# 08_Peripherral.net
KiCad netlist of a schematic drawn in Altium Designer
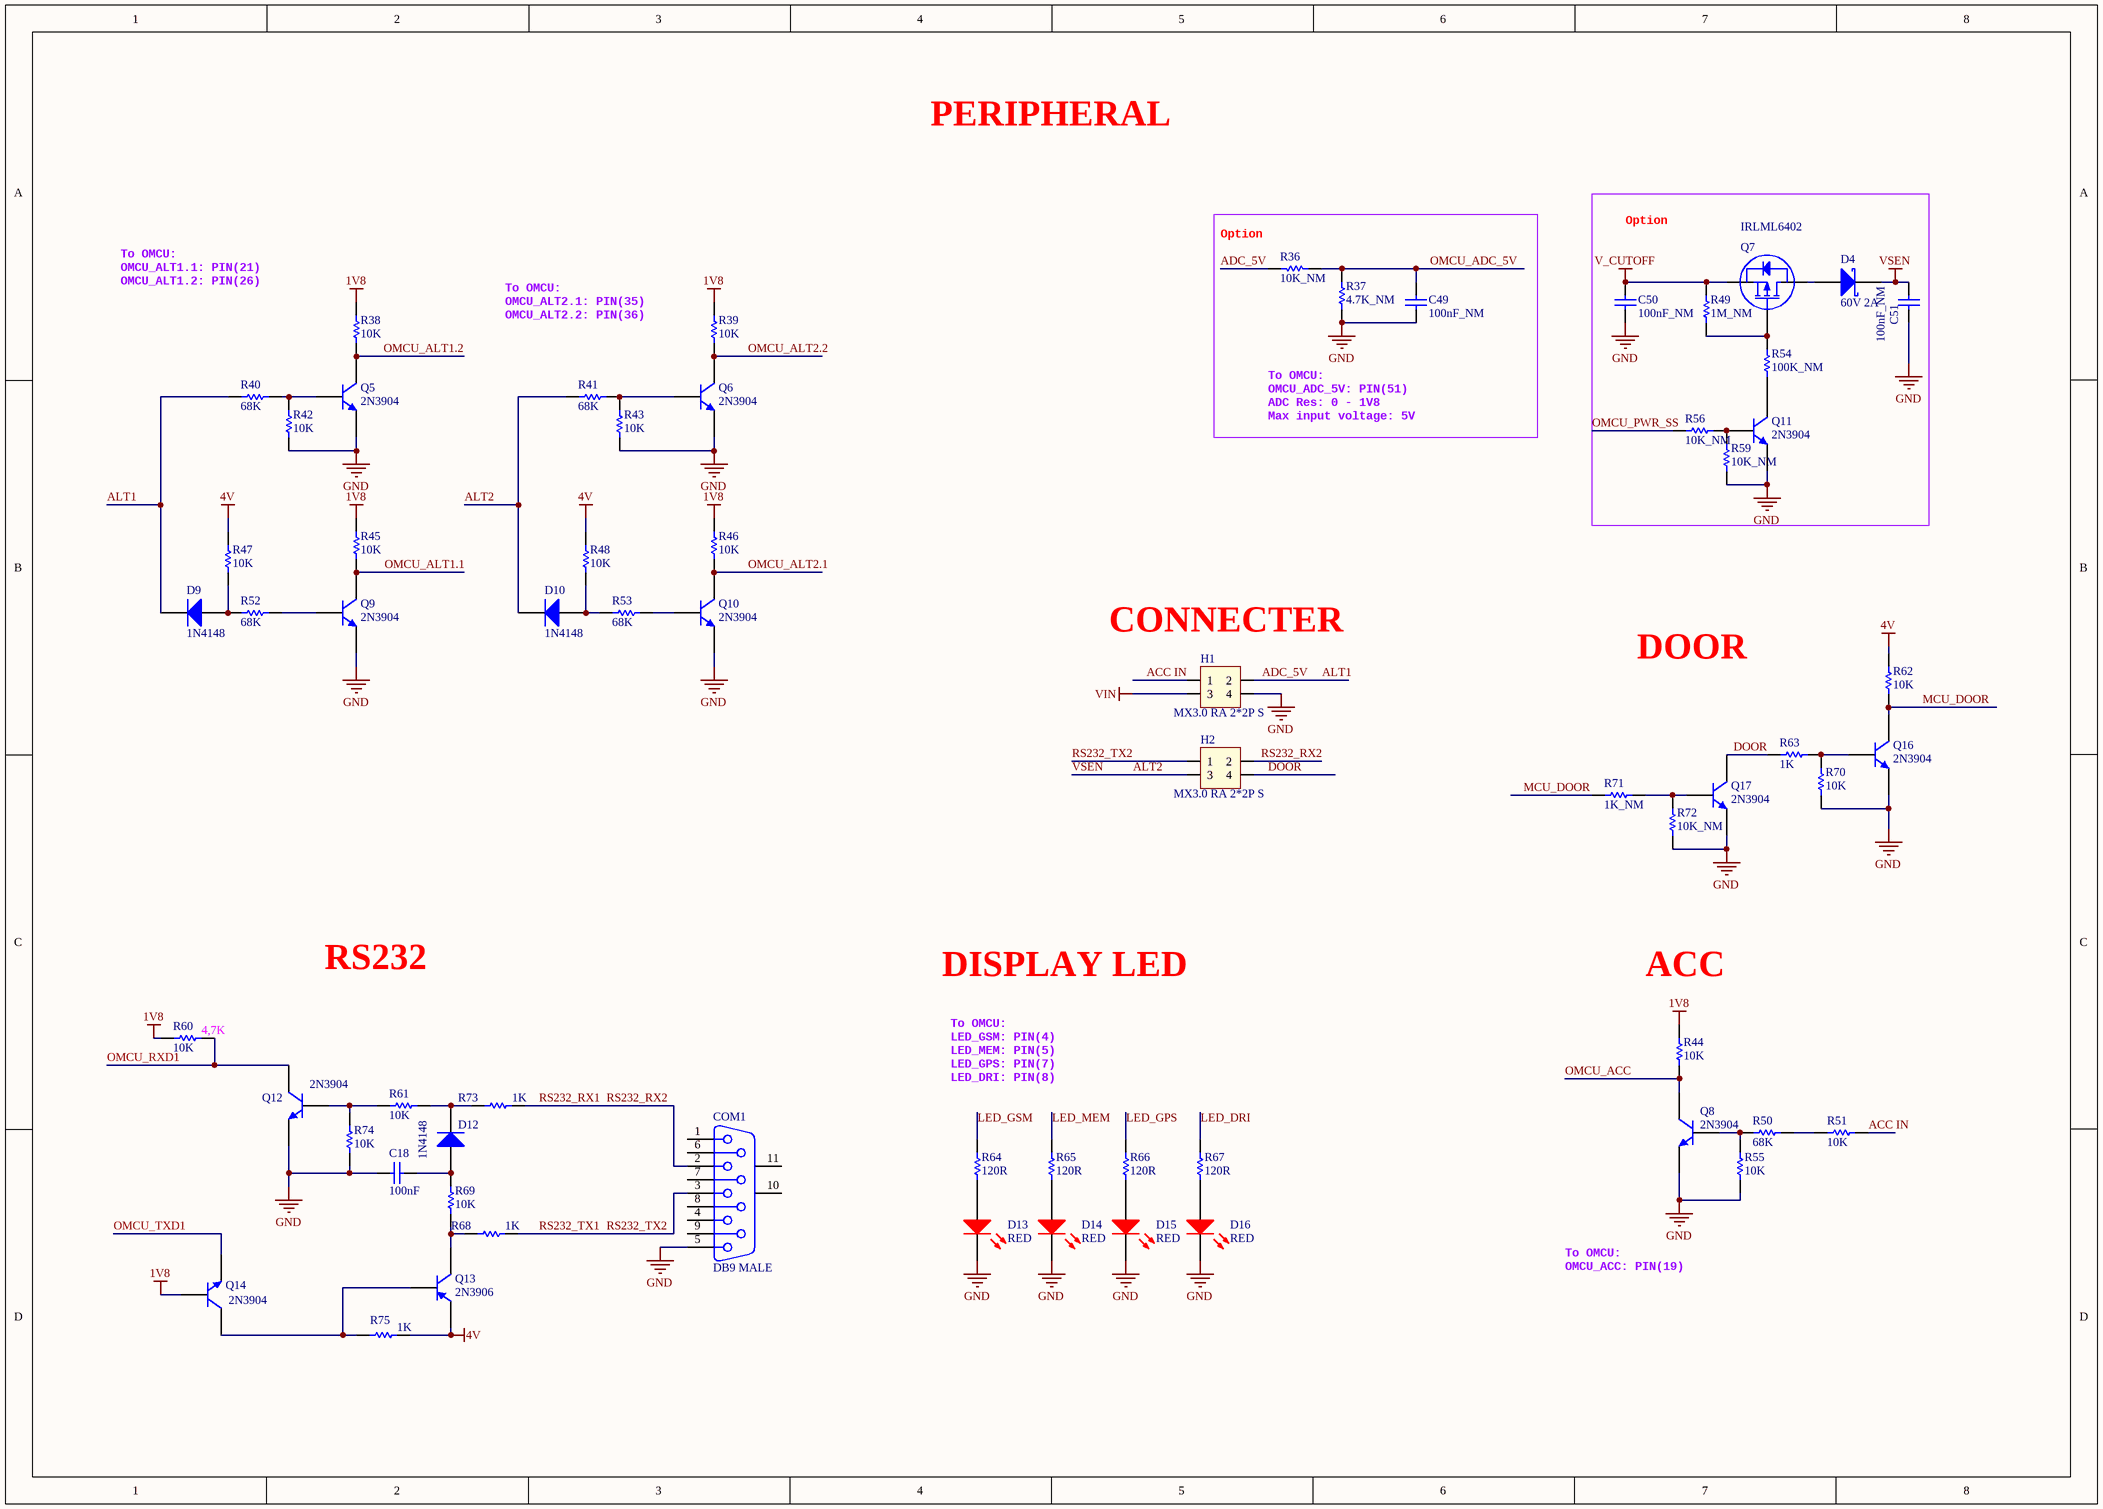
[diagram p0: 08 Peripherral.SchDoc]

(export (version "E")
  (design (tool "Eeschema 10.0.6"))
  (components
    (comp (ref "C18")
      (value "100nF")
      (footprint "0603 - C")
      (description "CAP CER 100nF 50V C0G/NP0 0603")
      (fields (field (name "MPN") "CL10C104JB8NNNC") (field (name "MFR") "SAMSUNG"))
      (libsource (lib "Library_Chip") (part "Cap 0603 100nF"))
    )
    (comp (ref "C49")
      (value "100nF_NM")
      (footprint "0603 - C")
      (description "CAP CER 100nF 50V C0G/NP0 0603")
      (fields (field (name "VOLTAGE") "50V") (field (name "MPN") "CL10C104JB8NNNC"))
      (libsource (lib "Library_Chip") (part "Cap 0603 100nF"))
    )
    (comp (ref "C50")
      (value "100nF_NM")
      (footprint "0603 - C")
      (description "CAP CER 100nF 50V C0G/NP0 0603")
      (fields (field (name "MPN") "CL10C104JB8NNNC") (field (name "MFR") "SAMSUNG"))
      (libsource (lib "Library_Chip") (part "Cap 0603 100nF"))
    )
    (comp (ref "C51")
      (value "100nF_NM")
      (footprint "0603 - C")
      (description "CAP CER 100nF 50V C0G/NP0 0603")
      (fields (field (name "MPN") "CL10C104JB8NNNC") (field (name "MFR") "SAMSUNG"))
      (libsource (lib "Library_Chip") (part "Cap 0603 100nF"))
    )
    (comp (ref "COM1")
      (value "DB9 MALE")
      (footprint "DSB 9M-SM")
      (description "CONN D-SUB PLUG 9POS PNL MNT")
      (fields (field (name "MPN") "772-E09-103R001") (field (name "MFR") "Norcomp Inc."))
      (libsource (lib "Library_ Connector") (part "DB9M S"))
    )
    (comp (ref "D4")
      (value "60V 2A")
      (footprint "SOD-123")
      (description "DIODE SCHOTTKY 60V 2A SOD123W")
      (fields (field (name "MPN") "PMEG6020ER,115") (field (name "MFR") "NXP"))
      (libsource (lib "Library_Chip") (part "Diode PMEG6020ER"))
    )
    (comp (ref "D9")
      (value "1N4148")
      (footprint "SOD-123")
      (description "DIODE GEN PURP 100V 300MA SOD123")
      (fields (field (name "MPN") "1N4148W-7-F") (field (name "MFR") "DIODES"))
      (libsource (lib "Library_Chip") (part "Diode 1N4148"))
    )
    (comp (ref "D10")
      (value "1N4148")
      (footprint "SOD-123")
      (description "DIODE GEN PURP 100V 300MA SOD123")
      (fields (field (name "MPN") "1N4148W-7-F") (field (name "MFR") "DIODES"))
      (libsource (lib "Library_Chip") (part "Diode 1N4148"))
    )
    (comp (ref "D12")
      (value "1N4148")
      (footprint "SOD-123")
      (description "DIODE GEN PURP 100V 300MA SOD123")
      (fields (field (name "MPN") "1N4148W-7-F") (field (name "MFR") "DIODES"))
      (libsource (lib "Library_Chip") (part "Diode 1N4148"))
    )
    (comp (ref "D13")
      (value "RED")
      (footprint "LED - 0603 - R")
      (description "LED RED CLEAR 0603 SMD")
      (fields (field (name "MFR") "Everlight") (field (name "MPN") "QTLP601CRTR"))
      (libsource (lib "Library_Chip") (part "LED 0603 RED"))
    )
    (comp (ref "D14")
      (value "RED")
      (footprint "LED - 0603 - R")
      (description "LED RED CLEAR 0603 SMD")
      (fields (field (name "MFR") "Everlight") (field (name "MPN") "QTLP601CRTR"))
      (libsource (lib "Library_Chip") (part "LED 0603 RED"))
    )
    (comp (ref "D15")
      (value "RED")
      (footprint "LED - 0603 - R")
      (description "LED RED CLEAR 0603 SMD")
      (fields (field (name "MFR") "Everlight") (field (name "MPN") "QTLP601CRTR"))
      (libsource (lib "Library_Chip") (part "LED 0603 RED"))
    )
    (comp (ref "D16")
      (value "RED")
      (footprint "LED - 0603 - R")
      (description "LED RED CLEAR 0603 SMD")
      (fields (field (name "MFR") "Everlight") (field (name "MPN") "QTLP601CRTR"))
      (libsource (lib "Library_Chip") (part "LED 0603 RED"))
    )
    (comp (ref "H1")
      (value "MX3.0 RA 2*2P S")
      (footprint "43045-M3045-2x2-B")
      (description "Micro-Fit 3.0™ Straight Header, 3.00mm Pitch, Dual Row, 4 Circuits")
      (fields (field (name "MPN") "M3045-2x2-B") (field (name "MFR") "China"))
      (libsource (lib "Library_ Connector") (part "HD2x2 S"))
    )
    (comp (ref "H2")
      (value "MX3.0 RA 2*2P S")
      (footprint "43045-M3045-2x2-B")
      (description "Micro-Fit 3.0™ Straight Header, 3.00mm Pitch, Dual Row, 4 Circuits")
      (fields (field (name "MPN") "M3045-2x2-B") (field (name "MFR") "China"))
      (libsource (lib "Library_ Connector") (part "HD2x2 S"))
    )
    (comp (ref "Q5")
      (value "2N3904")
      (footprint "SOT23B")
      (description "TRANS NPN 40V 0.2A SOT-23")
      (fields (field (name "MPN") "MMBT3904") (field (name "MFR") "Fairchild"))
      (libsource (lib "Library_Chip") (part "Transistor 2N3904"))
    )
    (comp (ref "Q6")
      (value "2N3904")
      (footprint "SOT23B")
      (description "TRANS NPN 40V 0.2A SOT-23")
      (fields (field (name "MPN") "MMBT3904") (field (name "MFR") "Fairchild"))
      (libsource (lib "Library_Chip") (part "Transistor 2N3904"))
    )
    (comp (ref "Q7")
      (value "IRLML6402")
      (footprint "SOT23B")
      (description "MOSFET P-CH 30V 3.6A SOT-23-3")
      (fields (field (name "MPN") "IRLML6402TRPBF") (field (name "MFR") "Infineon Technologies"))
      (libsource (lib "Library") (part "IRLML6402TRPBF"))
    )
    (comp (ref "Q8")
      (value "2N3904")
      (footprint "SOT23B")
      (description "TRANS NPN 40V 0.2A SOT-23")
      (fields (field (name "MPN") "MMBT3904") (field (name "MFR") "Fairchild"))
      (libsource (lib "Library_Chip") (part "Transistor 2N3904"))
    )
    (comp (ref "Q9")
      (value "2N3904")
      (footprint "SOT23B")
      (description "TRANS NPN 40V 0.2A SOT-23")
      (fields (field (name "MPN") "MMBT3904") (field (name "MFR") "Fairchild"))
      (libsource (lib "Library_Chip") (part "Transistor 2N3904"))
    )
    (comp (ref "Q10")
      (value "2N3904")
      (footprint "SOT23B")
      (description "TRANS NPN 40V 0.2A SOT-23")
      (fields (field (name "MPN") "MMBT3904") (field (name "MFR") "Fairchild"))
      (libsource (lib "Library_Chip") (part "Transistor 2N3904"))
    )
    (comp (ref "Q11")
      (value "2N3904")
      (footprint "SOT23B")
      (description "TRANS NPN 40V 0.2A SOT-23")
      (fields (field (name "MPN") "MMBT3904") (field (name "MFR") "Fairchild"))
      (libsource (lib "Library_Chip") (part "Transistor 2N3904"))
    )
    (comp (ref "Q12")
      (value "2N3904")
      (footprint "SOT23B")
      (description "TRANS NPN 40V 0.2A SOT-23")
      (fields (field (name "MPN") "MMBT3904") (field (name "MFR") "Fairchild"))
      (libsource (lib "Library_Chip") (part "Transistor 2N3904"))
    )
    (comp (ref "Q13")
      (value "2N3906")
      (footprint "SOT23B")
      (description "TRANS PNP 40V 0.2A SOT23")
      (fields (field (name "MPN") "MMBT3906") (field (name "MFR") "Fairchild"))
      (libsource (lib "Library_Chip") (part "Transistor 2N3906"))
    )
    (comp (ref "Q14")
      (value "2N3904")
      (footprint "SOT23B")
      (description "TRANS NPN 40V 0.2A SOT-23")
      (fields (field (name "MPN") "MMBT3904") (field (name "MFR") "Fairchild"))
      (libsource (lib "Library_Chip") (part "Transistor 2N3904"))
    )
    (comp (ref "Q16")
      (value "2N3904")
      (footprint "SOT23B")
      (description "TRANS NPN 40V 0.2A SOT-23")
      (fields (field (name "MPN") "MMBT3904") (field (name "MFR") "Fairchild"))
      (libsource (lib "Library_Chip") (part "Transistor 2N3904"))
    )
    (comp (ref "Q17")
      (value "2N3904")
      (footprint "SOT23B")
      (description "TRANS NPN 40V 0.2A SOT-23")
      (fields (field (name "MPN") "MMBT3904") (field (name "MFR") "Fairchild"))
      (libsource (lib "Library_Chip") (part "Transistor 2N3904"))
    )
    (comp (ref "R36")
      (value "10K_NM")
      (footprint "0603 - R")
      (description "RES SMD 10K OHM 1% 1/10W 0603")
      (fields (field (name "MFR") "Yageo") (field (name "MPN") "RC0603FR-0710KL"))
      (libsource (lib "Library_Chip") (part "Res 0603 10K"))
    )
    (comp (ref "R37")
      (value "4.7K_NM")
      (footprint "0603 - R")
      (description "RES SMD 4.7K OHM 1% 1/10W 0603")
      (fields (field (name "MFR") "Yageo") (field (name "MPN") "RC0603FR-074K7L"))
      (libsource (lib "Library_Chip") (part "Res 0603 4.7K"))
    )
    (comp (ref "R38")
      (value "10K")
      (footprint "0603 - R")
      (description "RES SMD 10K OHM 1% 1/10W 0603")
      (fields (field (name "MFR") "Yageo") (field (name "MPN") "RC0603FR-0710KL"))
      (libsource (lib "Library_Chip") (part "Res 0603 10K"))
    )
    (comp (ref "R39")
      (value "10K")
      (footprint "0603 - R")
      (description "RES SMD 10K OHM 1% 1/10W 0603")
      (fields (field (name "MFR") "Yageo") (field (name "MPN") "RC0603FR-0710KL"))
      (libsource (lib "Library_Chip") (part "Res 0603 10K"))
    )
    (comp (ref "R40")
      (value "68K")
      (footprint "0603 - R")
      (description "RES SMD 68K OHM 1% 1/10W 0603")
      (fields (field (name "MFR") "Yageo") (field (name "MPN") "RC0603FR-0768KL"))
      (libsource (lib "Library_Chip") (part "Res 0603 68K"))
    )
    (comp (ref "R41")
      (value "68K")
      (footprint "0603 - R")
      (description "RES SMD 68K OHM 1% 1/10W 0603")
      (fields (field (name "MFR") "Yageo") (field (name "MPN") "RC0603FR-0768KL"))
      (libsource (lib "Library_Chip") (part "Res 0603 68K"))
    )
    (comp (ref "R42")
      (value "10K")
      (footprint "0603 - R")
      (description "RES SMD 10K OHM 1% 1/10W 0603")
      (fields (field (name "MFR") "Yageo") (field (name "MPN") "RC0603FR-0710KL"))
      (libsource (lib "Library_Chip") (part "Res 0603 10K"))
    )
    (comp (ref "R43")
      (value "10K")
      (footprint "0603 - R")
      (description "RES SMD 10K OHM 1% 1/10W 0603")
      (fields (field (name "MFR") "Yageo") (field (name "MPN") "RC0603FR-0710KL"))
      (libsource (lib "Library_Chip") (part "Res 0603 10K"))
    )
    (comp (ref "R44")
      (value "10K")
      (footprint "0603 - R")
      (description "RES SMD 10K OHM 1% 1/10W 0603")
      (fields (field (name "MFR") "Yageo") (field (name "MPN") "RC0603FR-0710KL"))
      (libsource (lib "Library_Chip") (part "Res 0603 10K"))
    )
    (comp (ref "R45")
      (value "10K")
      (footprint "0603 - R")
      (description "RES SMD 10K OHM 1% 1/10W 0603")
      (fields (field (name "MFR") "Yageo") (field (name "MPN") "RC0603FR-0710KL"))
      (libsource (lib "Library_Chip") (part "Res 0603 10K"))
    )
    (comp (ref "R46")
      (value "10K")
      (footprint "0603 - R")
      (description "RES SMD 10K OHM 1% 1/10W 0603")
      (fields (field (name "MFR") "Yageo") (field (name "MPN") "RC0603FR-0710KL"))
      (libsource (lib "Library_Chip") (part "Res 0603 10K"))
    )
    (comp (ref "R47")
      (value "10K")
      (footprint "0603 - R")
      (description "RES SMD 10K OHM 1% 1/10W 0603")
      (fields (field (name "MFR") "Yageo") (field (name "MPN") "RC0603FR-0710KL"))
      (libsource (lib "Library_Chip") (part "Res 0603 10K"))
    )
    (comp (ref "R48")
      (value "10K")
      (footprint "0603 - R")
      (description "RES SMD 10K OHM 1% 1/10W 0603")
      (fields (field (name "MFR") "Yageo") (field (name "MPN") "RC0603FR-0710KL"))
      (libsource (lib "Library_Chip") (part "Res 0603 10K"))
    )
    (comp (ref "R49")
      (value "1M_NM")
      (footprint "0603 - R")
      (description "RES SMD 1M OHM 1% 1/10W 0603")
      (fields (field (name "MFR") "Yageo") (field (name "MPN") "RC0603FR-071ML"))
      (libsource (lib "Library_Chip") (part "Res 0603 1M"))
    )
    (comp (ref "R50")
      (value "68K")
      (footprint "0603 - R")
      (description "RES SMD 68K OHM 1% 1/10W 0603")
      (fields (field (name "MFR") "Yageo") (field (name "MPN") "RC0603FR-0768KL"))
      (libsource (lib "Library_Chip") (part "Res 0603 68K"))
    )
    (comp (ref "R51")
      (value "10K")
      (footprint "0603 - R")
      (description "RES SMD 10K OHM 1% 1/10W 0603")
      (fields (field (name "MFR") "Yageo") (field (name "MPN") "RC0603FR-0710KL"))
      (libsource (lib "Library_Chip") (part "Res 0603 10K"))
    )
    (comp (ref "R52")
      (value "68K")
      (footprint "0603 - R")
      (description "RES SMD 68K OHM 1% 1/10W 0603")
      (fields (field (name "MFR") "Yageo") (field (name "MPN") "RC0603FR-0768KL"))
      (libsource (lib "Library_Chip") (part "Res 0603 68K"))
    )
    (comp (ref "R53")
      (value "68K")
      (footprint "0603 - R")
      (description "RES SMD 68K OHM 1% 1/10W 0603")
      (fields (field (name "MFR") "Yageo") (field (name "MPN") "RC0603FR-0768KL"))
      (libsource (lib "Library_Chip") (part "Res 0603 68K"))
    )
    (comp (ref "R54")
      (value "100K_NM")
      (footprint "0603 - R")
      (description "RES SMD 100K OHM 1% 1/10W 0603")
      (fields (field (name "MFR") "Yageo") (field (name "MPN") "RC0603FR-07100KL"))
      (libsource (lib "Library_Chip") (part "Res 0603 100K"))
    )
    (comp (ref "R55")
      (value "10K")
      (footprint "0603 - R")
      (description "RES SMD 10K OHM 1% 1/10W 0603")
      (fields (field (name "MFR") "Yageo") (field (name "MPN") "RC0603FR-0710KL"))
      (libsource (lib "Library_Chip") (part "Res 0603 10K"))
    )
    (comp (ref "R56")
      (value "10K_NM")
      (footprint "0603 - R")
      (description "RES SMD 10K OHM 1% 1/10W 0603")
      (fields (field (name "MFR") "Yageo") (field (name "MPN") "RC0603FR-0710KL"))
      (libsource (lib "Library_Chip") (part "Res 0603 10K"))
    )
    (comp (ref "R59")
      (value "10K_NM")
      (footprint "0603 - R")
      (description "RES SMD 10K OHM 1% 1/10W 0603")
      (fields (field (name "MFR") "Yageo") (field (name "MPN") "RC0603FR-0710KL"))
      (libsource (lib "Library_Chip") (part "Res 0603 10K"))
    )
    (comp (ref "R60")
      (value "10K")
      (footprint "0603 - R")
      (description "RES SMD 10K OHM 1% 1/10W 0603")
      (fields (field (name "MFR") "Yageo") (field (name "MPN") "RC0603FR-0710KL"))
      (libsource (lib "Library_Chip") (part "Res 0603 10K"))
    )
    (comp (ref "R61")
      (value "10K")
      (footprint "0603 - R")
      (description "RES SMD 10K OHM 1% 1/10W 0603")
      (fields (field (name "MFR") "Yageo") (field (name "MPN") "RC0603FR-0710KL"))
      (libsource (lib "Library_Chip") (part "Res 0603 10K"))
    )
    (comp (ref "R62")
      (value "10K")
      (footprint "0603 - R")
      (description "RES SMD 10K OHM 1% 1/10W 0603")
      (fields (field (name "MFR") "Yageo") (field (name "MPN") "RC0603FR-0710KL"))
      (libsource (lib "Library_Chip") (part "Res 0603 10K"))
    )
    (comp (ref "R63")
      (value "1K")
      (footprint "0603 - R")
      (description "RES SMD 1K OHM 1% 1/10W 0603")
      (fields (field (name "MFR") "Yageo") (field (name "MPN") "RC0603FR-071KL"))
      (libsource (lib "Library_Chip") (part "Res 0603 1K"))
    )
    (comp (ref "R64")
      (value "120R")
      (footprint "0603 - R")
      (description "RES SMD 120 OHM 1% 1/10W 0603")
      (fields (field (name "MFR") "Yageo") (field (name "MPN") "AF0603FR-07120RL"))
      (libsource (lib "Library_Chip") (part "Res 0603 120R"))
    )
    (comp (ref "R65")
      (value "120R")
      (footprint "0603 - R")
      (description "RES SMD 120 OHM 1% 1/10W 0603")
      (fields (field (name "MFR") "Yageo") (field (name "MPN") "AF0603FR-07120RL"))
      (libsource (lib "Library_Chip") (part "Res 0603 120R"))
    )
    (comp (ref "R66")
      (value "120R")
      (footprint "0603 - R")
      (description "RES SMD 120 OHM 1% 1/10W 0603")
      (fields (field (name "MFR") "Yageo") (field (name "MPN") "AF0603FR-07120RL"))
      (libsource (lib "Library_Chip") (part "Res 0603 120R"))
    )
    (comp (ref "R67")
      (value "120R")
      (footprint "0603 - R")
      (description "RES SMD 120 OHM 1% 1/10W 0603")
      (fields (field (name "MFR") "Yageo") (field (name "MPN") "AF0603FR-07120RL"))
      (libsource (lib "Library_Chip") (part "Res 0603 120R"))
    )
    (comp (ref "R68")
      (value "1K")
      (footprint "0603 - R")
      (description "RES SMD 1K OHM 1% 1/10W 0603")
      (fields (field (name "MFR") "Yageo") (field (name "MPN") "RC0603FR-071KL"))
      (libsource (lib "Library_Chip") (part "Res 0603 1K"))
    )
    (comp (ref "R69")
      (value "10K")
      (footprint "0603 - R")
      (description "RES SMD 10K OHM 1% 1/10W 0603")
      (fields (field (name "MFR") "Yageo") (field (name "MPN") "RC0603FR-0710KL"))
      (libsource (lib "Library_Chip") (part "Res 0603 10K"))
    )
    (comp (ref "R70")
      (value "10K")
      (footprint "0603 - R")
      (description "RES SMD 10K OHM 1% 1/10W 0603")
      (fields (field (name "MFR") "Yageo") (field (name "MPN") "RC0603FR-0710KL"))
      (libsource (lib "Library_Chip") (part "Res 0603 10K"))
    )
    (comp (ref "R71")
      (value "1K_NM")
      (footprint "0603 - R")
      (description "RES SMD 1K OHM 1% 1/10W 0603")
      (fields (field (name "MFR") "Yageo") (field (name "MPN") "RC0603FR-071KL"))
      (libsource (lib "Library_Chip") (part "Res 0603 1K"))
    )
    (comp (ref "R72")
      (value "10K_NM")
      (footprint "0603 - R")
      (description "RES SMD 10K OHM 1% 1/10W 0603")
      (fields (field (name "MFR") "Yageo") (field (name "MPN") "RC0603FR-0710KL"))
      (libsource (lib "Library_Chip") (part "Res 0603 10K"))
    )
    (comp (ref "R73")
      (value "1K")
      (footprint "0603 - R")
      (description "RES SMD 1K OHM 1% 1/10W 0603")
      (fields (field (name "MFR") "Yageo") (field (name "MPN") "RC0603FR-071KL"))
      (libsource (lib "Library_Chip") (part "Res 0603 1K"))
    )
    (comp (ref "R74")
      (value "10K")
      (footprint "0603 - R")
      (description "RES SMD 10K OHM 1% 1/10W 0603")
      (fields (field (name "MFR") "Yageo") (field (name "MPN") "RC0603FR-0710KL"))
      (libsource (lib "Library_Chip") (part "Res 0603 10K"))
    )
    (comp (ref "R75")
      (value "1K")
      (footprint "0603 - R")
      (description "RES SMD 1K OHM 1% 1/10W 0603")
      (fields (field (name "MFR") "Yageo") (field (name "MPN") "RC0603FR-071KL"))
      (libsource (lib "Library_Chip") (part "Res 0603 1K"))
    )
  )
  (nets
    (net (code "1") (name "/ACC IN") (class "Default")
      (node (ref "H1") (pin "1") (pinfunction "1_1") (pintype "passive"))
      (node (ref "R51") (pin "2") (pinfunction "2_2") (pintype "passive"))
    )
    (net (code "2") (name "/ADC_5V") (class "Default")
      (node (ref "D9") (pin "2") (pinfunction "K_2") (pintype "passive"))
      (node (ref "H1") (pin "2") (pinfunction "2_2") (pintype "passive"))
      (node (ref "R36") (pin "2") (pinfunction "2_2") (pintype "passive"))
      (node (ref "R40") (pin "1") (pinfunction "1_1") (pintype "passive"))
    )
    (net (code "3") (name "/DOOR") (class "Default")
      (node (ref "H2") (pin "4") (pinfunction "4_4") (pintype "passive"))
      (node (ref "Q17") (pin "3") (pinfunction "C_3") (pintype "passive"))
      (node (ref "R63") (pin "1") (pinfunction "1_1") (pintype "passive"))
    )
    (net (code "4") (name "/LED_DRI") (class "Default")
      (node (ref "R67") (pin "2") (pinfunction "2_2") (pintype "passive"))
    )
    (net (code "5") (name "/LED_GPS") (class "Default")
      (node (ref "R66") (pin "2") (pinfunction "2_2") (pintype "passive"))
    )
    (net (code "6") (name "/LED_GSM") (class "Default")
      (node (ref "R64") (pin "2") (pinfunction "2_2") (pintype "passive"))
    )
    (net (code "7") (name "/LED_MEM") (class "Default")
      (node (ref "R65") (pin "2") (pinfunction "2_2") (pintype "passive"))
    )
    (net (code "8") (name "/MCU_DOOR") (class "Default")
      (node (ref "Q16") (pin "3") (pinfunction "C_3") (pintype "passive"))
      (node (ref "R62") (pin "1") (pinfunction "1_1") (pintype "passive"))
      (node (ref "R71") (pin "1") (pinfunction "1_1") (pintype "passive"))
    )
    (net (code "9") (name "/OMCU_ACC") (class "Default")
      (node (ref "Q8") (pin "3") (pinfunction "C_3") (pintype "passive"))
      (node (ref "R44") (pin "1") (pinfunction "1_1") (pintype "passive"))
    )
    (net (code "10") (name "/OMCU_ADC_5V") (class "Default")
      (node (ref "C49") (pin "2") (pinfunction "2_2") (pintype "passive"))
      (node (ref "R36") (pin "1") (pinfunction "1_1") (pintype "passive"))
      (node (ref "R37") (pin "2") (pinfunction "2_2") (pintype "passive"))
    )
    (net (code "11") (name "/OMCU_ALT1.1") (class "Default")
      (node (ref "Q9") (pin "3") (pinfunction "C_3") (pintype "passive"))
      (node (ref "R45") (pin "1") (pinfunction "1_1") (pintype "passive"))
    )
    (net (code "12") (name "/OMCU_ALT1.2") (class "Default")
      (node (ref "Q5") (pin "3") (pinfunction "C_3") (pintype "passive"))
      (node (ref "R38") (pin "1") (pinfunction "1_1") (pintype "passive"))
    )
    (net (code "13") (name "/OMCU_ALT2.1") (class "Default")
      (node (ref "Q10") (pin "3") (pinfunction "C_3") (pintype "passive"))
      (node (ref "R46") (pin "1") (pinfunction "1_1") (pintype "passive"))
    )
    (net (code "14") (name "/OMCU_ALT2.2") (class "Default")
      (node (ref "Q6") (pin "3") (pinfunction "C_3") (pintype "passive"))
      (node (ref "R39") (pin "1") (pinfunction "1_1") (pintype "passive"))
    )
    (net (code "15") (name "/OMCU_PWR_SS") (class "Default")
      (node (ref "R56") (pin "1") (pinfunction "1_1") (pintype "passive"))
    )
    (net (code "16") (name "/OMCU_RXD1") (class "Default")
      (node (ref "Q12") (pin "3") (pinfunction "C_3") (pintype "passive"))
      (node (ref "R60") (pin "1") (pinfunction "1_1") (pintype "passive"))
    )
    (net (code "17") (name "/OMCU_TXD1") (class "Default")
      (node (ref "Q14") (pin "2") (pinfunction "E_2") (pintype "passive"))
    )
    (net (code "18") (name "/RS232_RX1") (class "Default")
      (node (ref "COM1") (pin "2") (pinfunction "2_2") (pintype "passive"))
      (node (ref "H2") (pin "2") (pinfunction "2_2") (pintype "passive"))
      (node (ref "R73") (pin "2") (pinfunction "2_2") (pintype "passive"))
    )
    (net (code "19") (name "/RS232_TX1") (class "Default")
      (node (ref "COM1") (pin "3") (pinfunction "3_3") (pintype "passive"))
      (node (ref "H2") (pin "1") (pinfunction "1_1") (pintype "passive"))
      (node (ref "R68") (pin "2") (pinfunction "2_2") (pintype "passive"))
    )
    (net (code "20") (name "1V8") (class "Default")
      (node (ref "Q14") (pin "1") (pinfunction "B_1") (pintype "passive"))
      (node (ref "R38") (pin "2") (pinfunction "2_2") (pintype "passive"))
      (node (ref "R39") (pin "2") (pinfunction "2_2") (pintype "passive"))
      (node (ref "R44") (pin "2") (pinfunction "2_2") (pintype "passive"))
      (node (ref "R45") (pin "2") (pinfunction "2_2") (pintype "passive"))
      (node (ref "R46") (pin "2") (pinfunction "2_2") (pintype "passive"))
      (node (ref "R60") (pin "2") (pinfunction "2_2") (pintype "passive"))
    )
    (net (code "21") (name "4V") (class "Default")
      (node (ref "Q13") (pin "2") (pinfunction "E_2") (pintype "passive"))
      (node (ref "R47") (pin "2") (pinfunction "2_2") (pintype "passive"))
      (node (ref "R48") (pin "2") (pinfunction "2_2") (pintype "passive"))
      (node (ref "R62") (pin "2") (pinfunction "2_2") (pintype "passive"))
      (node (ref "R75") (pin "2") (pinfunction "2_2") (pintype "passive"))
    )
    (net (code "22") (name "GND") (class "Default")
      (node (ref "C18") (pin "1") (pinfunction "1_1") (pintype "passive"))
      (node (ref "C49") (pin "1") (pinfunction "1_1") (pintype "passive"))
      (node (ref "C50") (pin "1") (pinfunction "1_1") (pintype "passive"))
      (node (ref "C51") (pin "1") (pinfunction "1_1") (pintype "passive"))
      (node (ref "COM1") (pin "5") (pinfunction "5_5") (pintype "passive"))
      (node (ref "D13") (pin "2") (pinfunction "K_2") (pintype "passive"))
      (node (ref "D14") (pin "2") (pinfunction "K_2") (pintype "passive"))
      (node (ref "D15") (pin "2") (pinfunction "K_2") (pintype "passive"))
      (node (ref "D16") (pin "2") (pinfunction "K_2") (pintype "passive"))
      (node (ref "H1") (pin "4") (pinfunction "4_4") (pintype "passive"))
      (node (ref "Q10") (pin "2") (pinfunction "E_2") (pintype "passive"))
      (node (ref "Q11") (pin "2") (pinfunction "E_2") (pintype "passive"))
      (node (ref "Q12") (pin "2") (pinfunction "E_2") (pintype "passive"))
      (node (ref "Q16") (pin "2") (pinfunction "E_2") (pintype "passive"))
      (node (ref "Q17") (pin "2") (pinfunction "E_2") (pintype "passive"))
      (node (ref "Q5") (pin "2") (pinfunction "E_2") (pintype "passive"))
      (node (ref "Q6") (pin "2") (pinfunction "E_2") (pintype "passive"))
      (node (ref "Q8") (pin "2") (pinfunction "E_2") (pintype "passive"))
      (node (ref "Q9") (pin "2") (pinfunction "E_2") (pintype "passive"))
      (node (ref "R37") (pin "1") (pinfunction "1_1") (pintype "passive"))
      (node (ref "R42") (pin "1") (pinfunction "1_1") (pintype "passive"))
      (node (ref "R43") (pin "1") (pinfunction "1_1") (pintype "passive"))
      (node (ref "R55") (pin "2") (pinfunction "2_2") (pintype "passive"))
      (node (ref "R59") (pin "1") (pinfunction "1_1") (pintype "passive"))
      (node (ref "R70") (pin "1") (pinfunction "1_1") (pintype "passive"))
      (node (ref "R72") (pin "1") (pinfunction "1_1") (pintype "passive"))
      (node (ref "R74") (pin "2") (pinfunction "2_2") (pintype "passive"))
    )
    (net (code "23") (name "Net-(D4-A)") (class "Default")
      (node (ref "D4") (pin "1") (pinfunction "A_1") (pintype "passive"))
      (node (ref "Q7") (pin "3") (pinfunction "D_3") (pintype "passive"))
    )
    (net (code "24") (name "Net-(D9-A)") (class "Default")
      (node (ref "D9") (pin "1") (pinfunction "A_1") (pintype "passive"))
      (node (ref "R47") (pin "1") (pinfunction "1_1") (pintype "passive"))
      (node (ref "R52") (pin "1") (pinfunction "1_1") (pintype "passive"))
    )
    (net (code "25") (name "Net-(D10-A)") (class "Default")
      (node (ref "D10") (pin "1") (pinfunction "A_1") (pintype "passive"))
      (node (ref "R48") (pin "1") (pinfunction "1_1") (pintype "passive"))
      (node (ref "R53") (pin "1") (pinfunction "1_1") (pintype "passive"))
    )
    (net (code "26") (name "Net-(D12-A)") (class "Default")
      (node (ref "C18") (pin "2") (pinfunction "2_2") (pintype "passive"))
      (node (ref "D12") (pin "1") (pinfunction "A_1") (pintype "passive"))
      (node (ref "R69") (pin "1") (pinfunction "1_1") (pintype "passive"))
    )
    (net (code "27") (name "Net-(D12-K)") (class "Default")
      (node (ref "D12") (pin "2") (pinfunction "K_2") (pintype "passive"))
      (node (ref "R61") (pin "1") (pinfunction "1_1") (pintype "passive"))
      (node (ref "R73") (pin "1") (pinfunction "1_1") (pintype "passive"))
    )
    (net (code "28") (name "Net-(D13-A)") (class "Default")
      (node (ref "D13") (pin "1") (pinfunction "A_1") (pintype "passive"))
      (node (ref "R64") (pin "1") (pinfunction "1_1") (pintype "passive"))
    )
    (net (code "29") (name "Net-(D14-A)") (class "Default")
      (node (ref "D14") (pin "1") (pinfunction "A_1") (pintype "passive"))
      (node (ref "R65") (pin "1") (pinfunction "1_1") (pintype "passive"))
    )
    (net (code "30") (name "Net-(D15-A)") (class "Default")
      (node (ref "D15") (pin "1") (pinfunction "A_1") (pintype "passive"))
      (node (ref "R66") (pin "1") (pinfunction "1_1") (pintype "passive"))
    )
    (net (code "31") (name "Net-(D16-A)") (class "Default")
      (node (ref "D16") (pin "1") (pinfunction "A_1") (pintype "passive"))
      (node (ref "R67") (pin "1") (pinfunction "1_1") (pintype "passive"))
    )
    (net (code "32") (name "Net-(Q5-B)") (class "Default")
      (node (ref "Q5") (pin "1") (pinfunction "B_1") (pintype "passive"))
      (node (ref "R40") (pin "2") (pinfunction "2_2") (pintype "passive"))
      (node (ref "R42") (pin "2") (pinfunction "2_2") (pintype "passive"))
    )
    (net (code "33") (name "Net-(Q6-B)") (class "Default")
      (node (ref "Q6") (pin "1") (pinfunction "B_1") (pintype "passive"))
      (node (ref "R41") (pin "2") (pinfunction "2_2") (pintype "passive"))
      (node (ref "R43") (pin "2") (pinfunction "2_2") (pintype "passive"))
    )
    (net (code "34") (name "Net-(Q7-G)") (class "Default")
      (node (ref "Q7") (pin "1") (pinfunction "G_1") (pintype "passive"))
      (node (ref "R49") (pin "1") (pinfunction "1_1") (pintype "passive"))
      (node (ref "R54") (pin "2") (pinfunction "2_2") (pintype "passive"))
    )
    (net (code "35") (name "Net-(Q8-B)") (class "Default")
      (node (ref "Q8") (pin "1") (pinfunction "B_1") (pintype "passive"))
      (node (ref "R50") (pin "1") (pinfunction "1_1") (pintype "passive"))
      (node (ref "R55") (pin "1") (pinfunction "1_1") (pintype "passive"))
    )
    (net (code "36") (name "Net-(Q9-B)") (class "Default")
      (node (ref "Q9") (pin "1") (pinfunction "B_1") (pintype "passive"))
      (node (ref "R52") (pin "2") (pinfunction "2_2") (pintype "passive"))
    )
    (net (code "37") (name "Net-(Q10-B)") (class "Default")
      (node (ref "Q10") (pin "1") (pinfunction "B_1") (pintype "passive"))
      (node (ref "R53") (pin "2") (pinfunction "2_2") (pintype "passive"))
    )
    (net (code "38") (name "Net-(Q11-B)") (class "Default")
      (node (ref "Q11") (pin "1") (pinfunction "B_1") (pintype "passive"))
      (node (ref "R56") (pin "2") (pinfunction "2_2") (pintype "passive"))
      (node (ref "R59") (pin "2") (pinfunction "2_2") (pintype "passive"))
    )
    (net (code "39") (name "Net-(Q11-C)") (class "Default")
      (node (ref "Q11") (pin "3") (pinfunction "C_3") (pintype "passive"))
      (node (ref "R54") (pin "1") (pinfunction "1_1") (pintype "passive"))
    )
    (net (code "40") (name "Net-(Q12-B)") (class "Default")
      (node (ref "Q12") (pin "1") (pinfunction "B_1") (pintype "passive"))
      (node (ref "R61") (pin "2") (pinfunction "2_2") (pintype "passive"))
      (node (ref "R74") (pin "1") (pinfunction "1_1") (pintype "passive"))
    )
    (net (code "41") (name "Net-(Q13-B)") (class "Default")
      (node (ref "Q13") (pin "1") (pinfunction "B_1") (pintype "passive"))
      (node (ref "Q14") (pin "3") (pinfunction "C_3") (pintype "passive"))
      (node (ref "R75") (pin "1") (pinfunction "1_1") (pintype "passive"))
    )
    (net (code "42") (name "Net-(Q13-C)") (class "Default")
      (node (ref "Q13") (pin "3") (pinfunction "C_3") (pintype "passive"))
      (node (ref "R68") (pin "1") (pinfunction "1_1") (pintype "passive"))
      (node (ref "R69") (pin "2") (pinfunction "2_2") (pintype "passive"))
    )
    (net (code "43") (name "Net-(Q16-B)") (class "Default")
      (node (ref "Q16") (pin "1") (pinfunction "B_1") (pintype "passive"))
      (node (ref "R63") (pin "2") (pinfunction "2_2") (pintype "passive"))
      (node (ref "R70") (pin "2") (pinfunction "2_2") (pintype "passive"))
    )
    (net (code "44") (name "Net-(Q17-B)") (class "Default")
      (node (ref "Q17") (pin "1") (pinfunction "B_1") (pintype "passive"))
      (node (ref "R71") (pin "2") (pinfunction "2_2") (pintype "passive"))
      (node (ref "R72") (pin "2") (pinfunction "2_2") (pintype "passive"))
    )
    (net (code "45") (name "Net-(R50-Pad2)") (class "Default")
      (node (ref "R50") (pin "2") (pinfunction "2_2") (pintype "passive"))
      (node (ref "R51") (pin "1") (pinfunction "1_1") (pintype "passive"))
    )
    (net (code "46") (name "VIN") (class "Default")
      (node (ref "H1") (pin "3") (pinfunction "3_3") (pintype "passive"))
    )
    (net (code "47") (name "VSEN") (class "Default")
      (node (ref "C51") (pin "2") (pinfunction "2_2") (pintype "passive"))
      (node (ref "D10") (pin "2") (pinfunction "K_2") (pintype "passive"))
      (node (ref "D4") (pin "2") (pinfunction "K_2") (pintype "passive"))
      (node (ref "H2") (pin "3") (pinfunction "3_3") (pintype "passive"))
      (node (ref "R41") (pin "1") (pinfunction "1_1") (pintype "passive"))
    )
    (net (code "48") (name "V_CUTOFF") (class "Default")
      (node (ref "C50") (pin "2") (pinfunction "2_2") (pintype "passive"))
      (node (ref "Q7") (pin "2") (pinfunction "S_2") (pintype "passive"))
      (node (ref "R49") (pin "2") (pinfunction "2_2") (pintype "passive"))
    )
    (net (code "49") (name "unconnected-(COM1-MH1-Pad10)") (class "Default")
      (node (ref "COM1") (pin "10") (pinfunction "MH1_10") (pintype "passive"))
    )
    (net (code "50") (name "unconnected-(COM1-MH2-Pad11)") (class "Default")
      (node (ref "COM1") (pin "11") (pinfunction "MH2_11") (pintype "passive"))
    )
    (net (code "51") (name "unconnected-(COM1-Pad1)") (class "Default")
      (node (ref "COM1") (pin "1") (pinfunction "1_1") (pintype "passive"))
    )
    (net (code "52") (name "unconnected-(COM1-Pad4)") (class "Default")
      (node (ref "COM1") (pin "4") (pinfunction "4_4") (pintype "passive"))
    )
    (net (code "53") (name "unconnected-(COM1-Pad6)") (class "Default")
      (node (ref "COM1") (pin "6") (pinfunction "6_6") (pintype "passive"))
    )
    (net (code "54") (name "unconnected-(COM1-Pad7)") (class "Default")
      (node (ref "COM1") (pin "7") (pinfunction "7_7") (pintype "passive"))
    )
    (net (code "55") (name "unconnected-(COM1-Pad8)") (class "Default")
      (node (ref "COM1") (pin "8") (pinfunction "8_8") (pintype "passive"))
    )
    (net (code "56") (name "unconnected-(COM1-Pad9)") (class "Default")
      (node (ref "COM1") (pin "9") (pinfunction "9_9") (pintype "passive"))
    )
  )
)
